# ProPrj_elrsTransmitter_2026-04-23.net
KiCad netlist of a schematic drawn in EasyEDA Pro
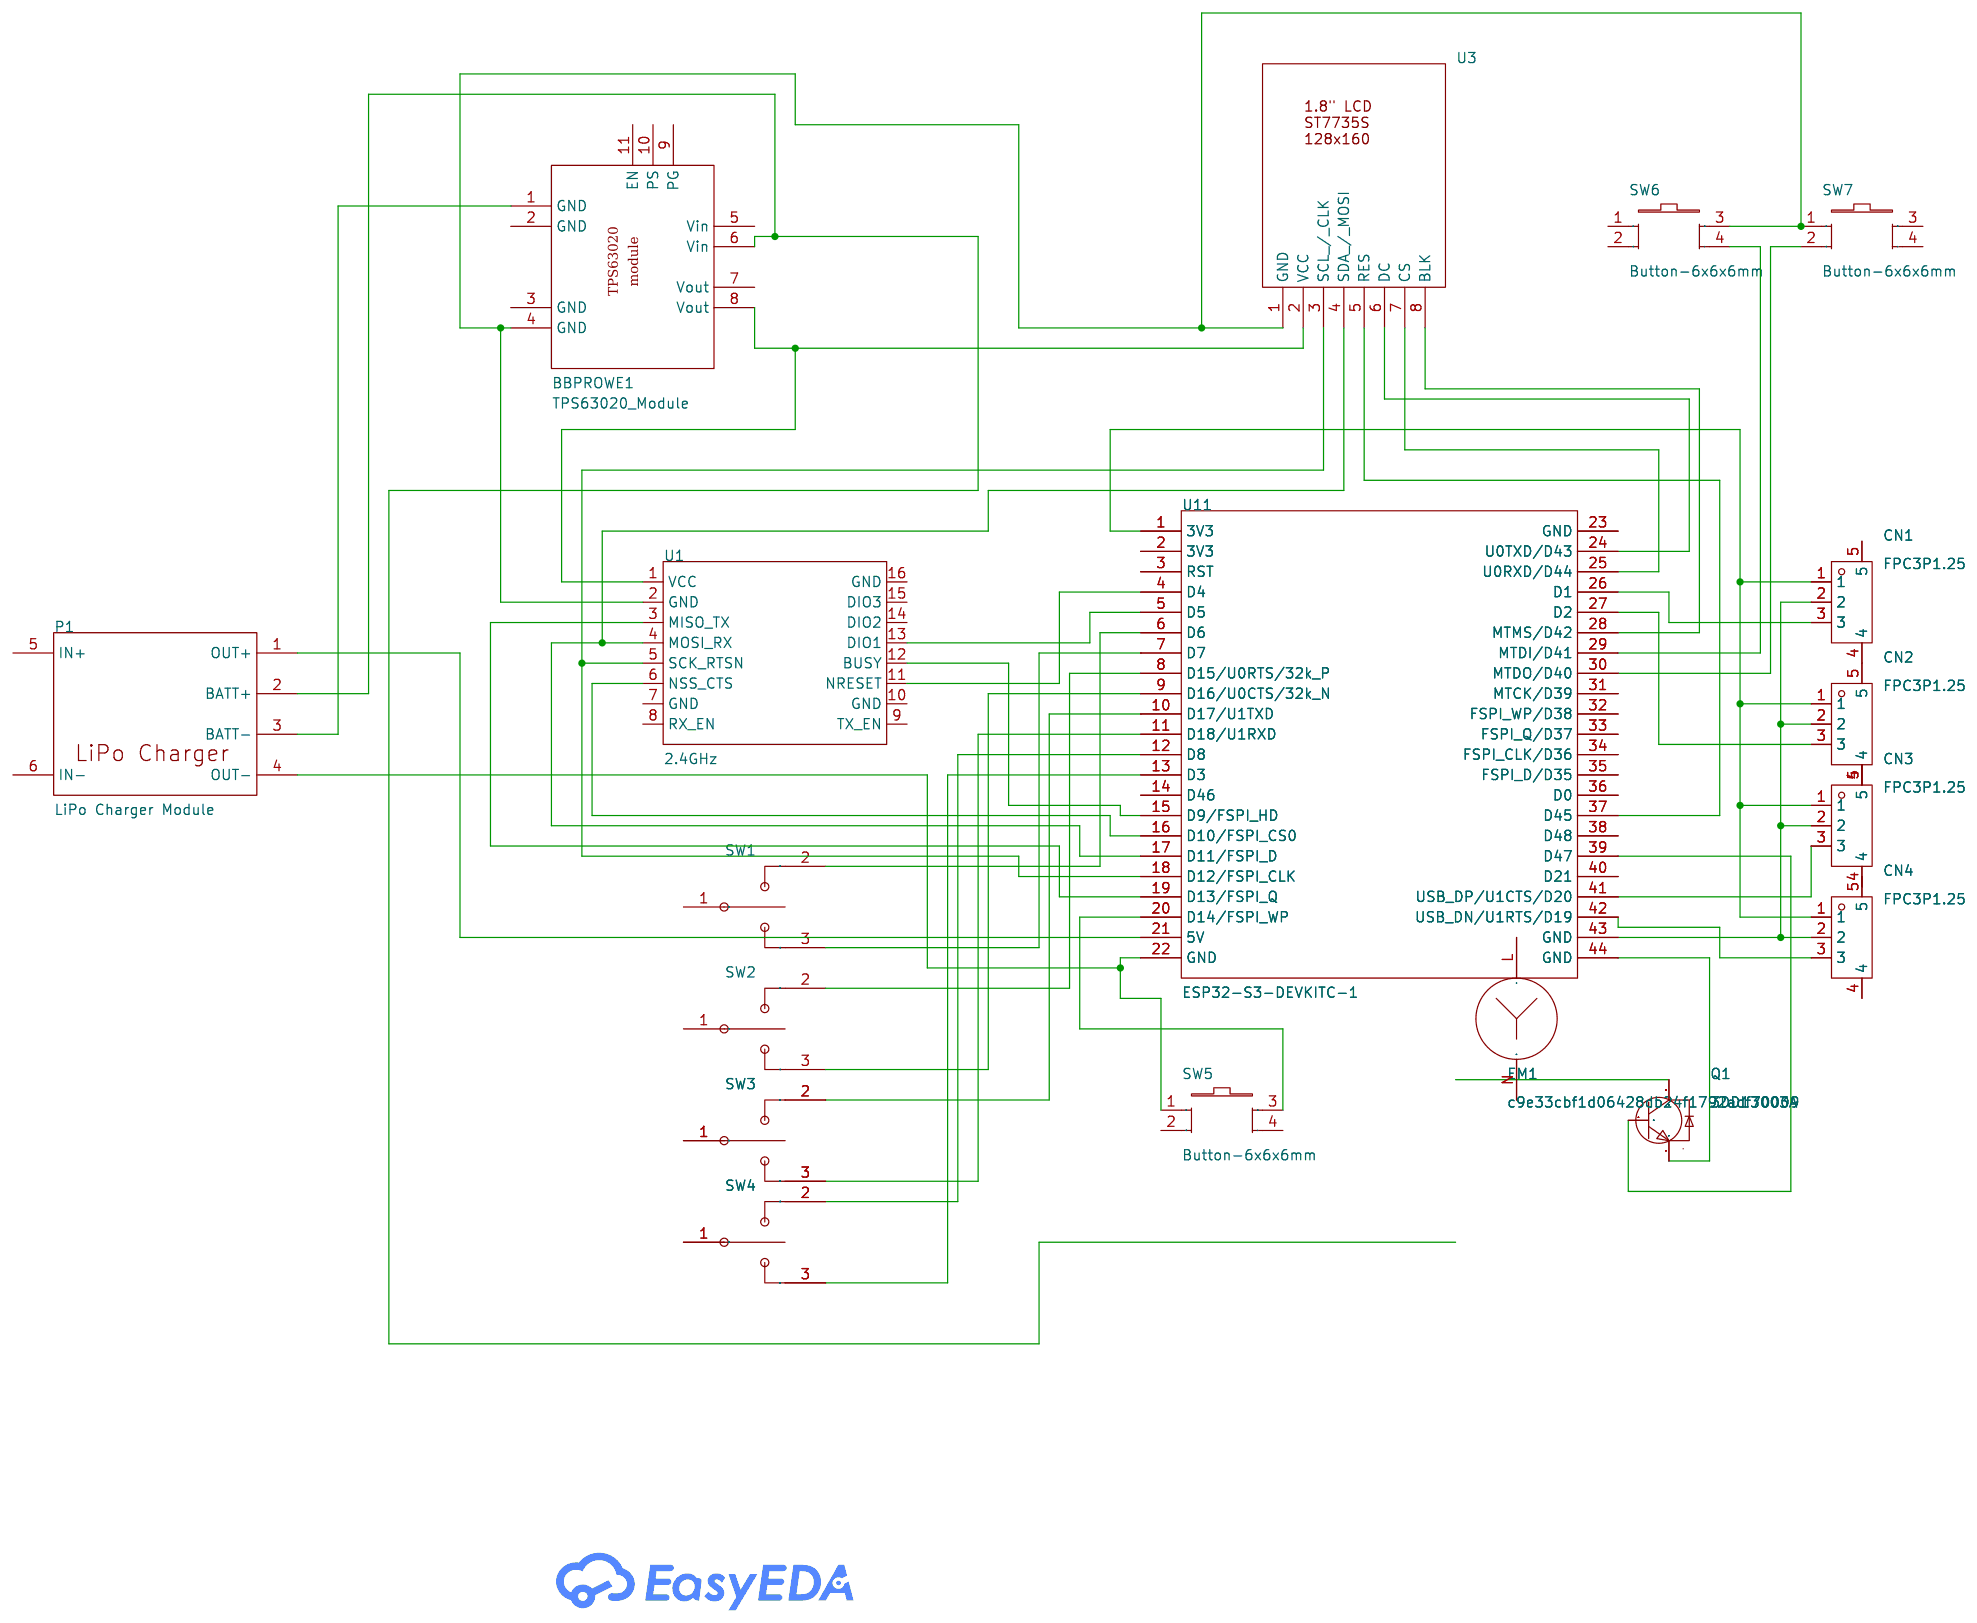
[diagram p0: schematic sheet]

(export (version "E")
  (design (tool "Eeschema 10.0.6"))
  (components
    (comp (ref "BBPROWE1")
      (value "TPS63020_Module")
      (footprint "easyedapro:TPS63020_MODULE_PCB")
      (libsource (lib "easyedapro") (part "TPS63020_Module"))
    )
    (comp (ref "CN1")
      (value "FPC3P1.25")
      (footprint "easyedapro:CONN-SMD_3P-P1.25_1.25T-3PWT")
      (libsource (lib "easyedapro") (part "FPC3P1.25"))
    )
    (comp (ref "CN2")
      (value "FPC3P1.25")
      (footprint "easyedapro:CONN-SMD_3P-P1.25_1.25T-3PWT")
      (libsource (lib "easyedapro") (part "FPC3P1.25"))
    )
    (comp (ref "CN3")
      (value "FPC3P1.25")
      (footprint "easyedapro:CONN-SMD_3P-P1.25_1.25T-3PWT")
      (libsource (lib "easyedapro") (part "FPC3P1.25"))
    )
    (comp (ref "CN4")
      (value "FPC3P1.25")
      (footprint "easyedapro:CONN-SMD_3P-P1.25_1.25T-3PWT")
      (libsource (lib "easyedapro") (part "FPC3P1.25"))
    )
    (comp (ref "EM1")
      (value "c9e33cbf1d06428db24f1792adf70009")
      (description "GVI AC Fan for half size server rack")
      (fields (field (name "Manufacturer") "GVI"))
      (libsource (lib "easyedapro") (part "GVI AC Fan"))
    )
    (comp (ref "P1")
      (value "LiPo Charger Module")
      (footprint "easyedapro:LIPO CHARGER FOOTPRINT")
      (libsource (lib "easyedapro") (part "Charger Lipo"))
    )
    (comp (ref "Q1")
      (value "3DD13003A")
      (footprint "easyedapro:TO-92-3_L4.8-W3.7-P1.27-L")
      (fields (field (name "Manufacturer") "吉林华微"))
      (libsource (lib "easyedapro") (part "3DD13003A"))
    )
    (comp (ref "SW1")
      (value "~")
      (footprint "easyedapro:3_Pin_Toggle_Switch_Footprint")
      (libsource (lib "easyedapro") (part "3_Position_Toggle_Switch"))
    )
    (comp (ref "SW2")
      (value "~")
      (footprint "easyedapro:3_Pin_Toggle_Switch_Footprint")
      (libsource (lib "easyedapro") (part "3_Position_Toggle_Switch"))
    )
    (comp (ref "SW3")
      (value "~")
      (footprint "easyedapro:3_Pin_Toggle_Switch_Footprint")
      (libsource (lib "easyedapro") (part "3_Position_Toggle_Switch"))
    )
    (comp (ref "SW4")
      (value "~")
      (footprint "easyedapro:3_Pin_Toggle_Switch_Footprint")
      (libsource (lib "easyedapro") (part "3_Position_Toggle_Switch"))
    )
    (comp (ref "SW5")
      (value "Button-6x6x6mm")
      (footprint "easyedapro:SW-TH_4PIN-L6.00-W6.00")
      (fields
        (field (name "Manufacturer Part") "Switch,6*6*6Plastic head,260G, 0.25mm,Straight line")
        (field (name "Manufacturer") "BBJ")
      )
      (libsource (lib "easyedapro") (part "Button-6x6x6mm"))
    )
    (comp (ref "SW6")
      (value "Button-6x6x6mm")
      (footprint "easyedapro:SW-TH_4PIN-L6.00-W6.00")
      (fields
        (field (name "Manufacturer Part") "Switch,6*6*6Plastic head,260G, 0.25mm,Straight line")
        (field (name "Manufacturer") "BBJ")
      )
      (libsource (lib "easyedapro") (part "Button-6x6x6mm"))
    )
    (comp (ref "SW7")
      (value "Button-6x6x6mm")
      (footprint "easyedapro:SW-TH_4PIN-L6.00-W6.00")
      (fields
        (field (name "Manufacturer Part") "Switch,6*6*6Plastic head,260G, 0.25mm,Straight line")
        (field (name "Manufacturer") "BBJ")
      )
      (libsource (lib "easyedapro") (part "Button-6x6x6mm"))
    )
    (comp (ref "U1")
      (value "2.4GHz")
      (footprint "easyedapro:WIRELM-SMD_E28-2G4M27SX")
      (description "Frequency:2.4GHz")
      (fields (field (name "Manufacturer Part") "E28-2G4M27SX") (field (name "Manufacturer") "EBYTE(亿佰特)"))
      (libsource (lib "easyedapro") (part "E28-2G4M27SX"))
    )
    (comp (ref "U3")
      (value "~")
      (footprint "easyedapro:WeAct 1.8 inch TFT ST7735S")
      (libsource (lib "easyedapro") (part "IPS_LCD_1.8_ST7735S_128x160"))
    )
    (comp (ref "U11")
      (value "ESP32-S3-DEVKITC-1")
      (footprint "easyedapro:ESP32-S3-DEVKITC-1")
      (fields
        (field (name "Manufacturer Part") "ESP32-S3-DEVKITC-1U-N8R8")
        (field (name "Manufacturer") "Espressif")
      )
      (libsource (lib "easyedapro") (part "ESP32-S3-DEVKITC-1"))
    )
  )
  (nets
    (net (code "1") (name "Net-(CN1-Pad1)") (class "Default")
      (node (ref "CN1") (pin "1") (pinfunction "1_1") (pintype "unspecified"))
      (node (ref "CN2") (pin "1") (pinfunction "1_1") (pintype "unspecified"))
      (node (ref "CN3") (pin "1") (pinfunction "1_1") (pintype "unspecified"))
      (node (ref "CN4") (pin "1") (pinfunction "1_1") (pintype "unspecified"))
      (node (ref "U11") (pin "1") (pinfunction "3V3_1") (pintype "input"))
    )
    (net (code "2") (name "Net-(CN1-Pad2)") (class "Default")
      (node (ref "CN1") (pin "2") (pinfunction "2_2") (pintype "unspecified"))
      (node (ref "CN2") (pin "2") (pinfunction "2_2") (pintype "unspecified"))
      (node (ref "CN3") (pin "2") (pinfunction "2_2") (pintype "unspecified"))
      (node (ref "CN4") (pin "2") (pinfunction "2_2") (pintype "unspecified"))
      (node (ref "U11") (pin "43") (pinfunction "GND_43") (pintype "input"))
    )
    (net (code "3") (name "Net-(CN1-Pad4)") (class "Default")
      (node (ref "CN1") (pin "4") (pinfunction "4_4") (pintype "unspecified"))
      (node (ref "CN2") (pin "5") (pinfunction "5_5") (pintype "unspecified"))
    )
    (net (code "4") (name "Net-(P1-BATT+)") (class "Default")
      (node (ref "BBPROWE1") (pin "6") (pinfunction "Vin_6") (pintype "input"))
      (node (ref "P1") (pin "2") (pinfunction "BATT+_2") (pintype "unspecified"))
    )
    (net (code "5") (name "Net-(P1-BATT-)") (class "Default")
      (node (ref "BBPROWE1") (pin "1") (pinfunction "GND_1") (pintype "input"))
      (node (ref "P1") (pin "3") (pinfunction "BATT-_3") (pintype "unspecified"))
    )
    (net (code "6") (name "Net-(P1-OUT+)") (class "Default")
      (node (ref "P1") (pin "1") (pinfunction "OUT+_1") (pintype "unspecified"))
      (node (ref "U11") (pin "21") (pinfunction "5V_21") (pintype "bidirectional"))
    )
    (net (code "7") (name "Net-(P1-OUT-)") (class "Default")
      (node (ref "P1") (pin "4") (pinfunction "OUT-_4") (pintype "unspecified"))
      (node (ref "SW5") (pin "1") (pinfunction "1_1") (pintype "input"))
      (node (ref "U11") (pin "22") (pinfunction "GND_22") (pintype "bidirectional"))
    )
    (net (code "8") (name "Net-(Q1-B)") (class "Default")
      (node (ref "Q1") (pin "3") (pinfunction "B_3") (pintype "unspecified"))
      (node (ref "U11") (pin "39") (pinfunction "D47_39") (pintype "input"))
    )
    (net (code "9") (name "Net-(Q1-E)") (class "Default")
      (node (ref "Q1") (pin "1") (pinfunction "E_1") (pintype "unspecified"))
      (node (ref "U11") (pin "44") (pinfunction "GND_44") (pintype "input"))
    )
    (net (code "10") (name "Net-(U1-BUSY)") (class "Default")
      (node (ref "U1") (pin "12") (pinfunction "BUSY_12") (pintype "unspecified"))
      (node (ref "U11") (pin "15") (pinfunction "D9/FSPI_HD_15") (pintype "bidirectional"))
    )
    (net (code "11") (name "Net-(U1-DIO1)") (class "Default")
      (node (ref "U1") (pin "13") (pinfunction "DIO1_13") (pintype "unspecified"))
      (node (ref "U11") (pin "5") (pinfunction "D5_5") (pintype "bidirectional"))
    )
    (net (code "12") (name "Net-(U1-MISO_TX)") (class "Default")
      (node (ref "U1") (pin "3") (pinfunction "MISO_TX_3") (pintype "unspecified"))
      (node (ref "U11") (pin "19") (pinfunction "D13/FSPI_Q_19") (pintype "input"))
    )
    (net (code "13") (name "Net-(U1-MOSI_RX)") (class "Default")
      (node (ref "U1") (pin "4") (pinfunction "MOSI_RX_4") (pintype "unspecified"))
      (node (ref "U11") (pin "17") (pinfunction "D11/FSPI_D_17") (pintype "bidirectional"))
      (node (ref "U3") (pin "4") (pinfunction "SDA_/_MOSI_4") (pintype "input"))
    )
    (net (code "14") (name "Net-(U1-NRESET)") (class "Default")
      (node (ref "U1") (pin "11") (pinfunction "NRESET_11") (pintype "unspecified"))
      (node (ref "U11") (pin "4") (pinfunction "D4_4") (pintype "bidirectional"))
    )
    (net (code "15") (name "Net-(U1-NSS_CTS)") (class "Default")
      (node (ref "U1") (pin "6") (pinfunction "NSS_CTS_6") (pintype "unspecified"))
      (node (ref "U11") (pin "16") (pinfunction "D10/FSPI_CS0_16") (pintype "bidirectional"))
    )
    (net (code "16") (name "Net-(U1-SCK_RTSN)") (class "Default")
      (node (ref "U1") (pin "5") (pinfunction "SCK_RTSN_5") (pintype "unspecified"))
      (node (ref "U11") (pin "18") (pinfunction "D12/FSPI_CLK_18") (pintype "input"))
      (node (ref "U3") (pin "3") (pinfunction "SCL_/_CLK_3") (pintype "input"))
    )
    (net (code "17") (name "Net-(U1-VCC)") (class "Default")
      (node (ref "BBPROWE1") (pin "8") (pinfunction "Vout_8") (pintype "input"))
      (node (ref "U1") (pin "1") (pinfunction "VCC_1") (pintype "unspecified"))
      (node (ref "U3") (pin "2") (pinfunction "VCC_2") (pintype "input"))
    )
    (net (code "18") (name "Net-(U3-GND)") (class "Default")
      (node (ref "BBPROWE1") (pin "4") (pinfunction "GND_4") (pintype "input"))
      (node (ref "SW6") (pin "3") (pinfunction "3_3") (pintype "input"))
      (node (ref "SW7") (pin "1") (pinfunction "1_1") (pintype "input"))
      (node (ref "U1") (pin "2") (pinfunction "GND_2") (pintype "unspecified"))
      (node (ref "U3") (pin "1") (pinfunction "GND_1") (pintype "input"))
    )
    (net (code "19") (name "Net-(U11-D1)") (class "Default")
      (node (ref "CN1") (pin "3") (pinfunction "3_3") (pintype "unspecified"))
      (node (ref "U11") (pin "26") (pinfunction "D1_26") (pintype "input"))
    )
    (net (code "20") (name "Net-(U11-D2)") (class "Default")
      (node (ref "CN2") (pin "3") (pinfunction "3_3") (pintype "unspecified"))
      (node (ref "U11") (pin "27") (pinfunction "D2_27") (pintype "bidirectional"))
    )
    (net (code "21") (name "Net-(U11-D3)") (class "Default")
      (node (ref "SW4") (pin "3") (pinfunction "3_3") (pintype "unspecified"))
      (node (ref "U11") (pin "13") (pinfunction "D3_13") (pintype "bidirectional"))
    )
    (net (code "22") (name "Net-(U11-D6)") (class "Default")
      (node (ref "SW1") (pin "2") (pinfunction "2_2") (pintype "unspecified"))
      (node (ref "U11") (pin "6") (pinfunction "D6_6") (pintype "bidirectional"))
    )
    (net (code "23") (name "Net-(U11-D7)") (class "Default")
      (node (ref "SW1") (pin "3") (pinfunction "3_3") (pintype "unspecified"))
      (node (ref "U11") (pin "7") (pinfunction "D7_7") (pintype "bidirectional"))
    )
    (net (code "24") (name "Net-(U11-D8)") (class "Default")
      (node (ref "SW4") (pin "2") (pinfunction "2_2") (pintype "unspecified"))
      (node (ref "U11") (pin "12") (pinfunction "D8_12") (pintype "bidirectional"))
    )
    (net (code "25") (name "Net-(U11-D14{slash}FSPI_WP)") (class "Default")
      (node (ref "SW5") (pin "3") (pinfunction "3_3") (pintype "input"))
      (node (ref "U11") (pin "20") (pinfunction "D14/FSPI_WP_20") (pintype "input"))
    )
    (net (code "26") (name "Net-(U11-D15{slash}U0RTS{slash}32k_P)") (class "Default")
      (node (ref "SW2") (pin "2") (pinfunction "2_2") (pintype "unspecified"))
      (node (ref "U11") (pin "8") (pinfunction "D15/U0RTS/32k_P_8") (pintype "bidirectional"))
    )
    (net (code "27") (name "Net-(U11-D16{slash}U0CTS{slash}32k_N)") (class "Default")
      (node (ref "SW2") (pin "3") (pinfunction "3_3") (pintype "unspecified"))
      (node (ref "U11") (pin "9") (pinfunction "D16/U0CTS/32k_N_9") (pintype "bidirectional"))
    )
    (net (code "28") (name "Net-(U11-D17{slash}U1TXD)") (class "Default")
      (node (ref "SW3") (pin "2") (pinfunction "2_2") (pintype "unspecified"))
      (node (ref "U11") (pin "10") (pinfunction "D17/U1TXD_10") (pintype "bidirectional"))
    )
    (net (code "29") (name "Net-(U11-D18{slash}U1RXD)") (class "Default")
      (node (ref "SW3") (pin "3") (pinfunction "3_3") (pintype "unspecified"))
      (node (ref "U11") (pin "11") (pinfunction "D18/U1RXD_11") (pintype "bidirectional"))
    )
    (net (code "30") (name "Net-(U11-D45)") (class "Default")
      (node (ref "U11") (pin "37") (pinfunction "D45_37") (pintype "bidirectional"))
      (node (ref "U3") (pin "5") (pinfunction "RES_5") (pintype "input"))
    )
    (net (code "31") (name "Net-(U11-MTDI{slash}D41)") (class "Default")
      (node (ref "SW6") (pin "4") (pinfunction "4_4") (pintype "input"))
      (node (ref "U11") (pin "29") (pinfunction "MTDI/D41_29") (pintype "bidirectional"))
    )
    (net (code "32") (name "Net-(U11-MTDO{slash}D40)") (class "Default")
      (node (ref "SW7") (pin "2") (pinfunction "2_2") (pintype "input"))
      (node (ref "U11") (pin "30") (pinfunction "MTDO/D40_30") (pintype "bidirectional"))
    )
    (net (code "33") (name "Net-(U11-MTMS{slash}D42)") (class "Default")
      (node (ref "U11") (pin "28") (pinfunction "MTMS/D42_28") (pintype "bidirectional"))
      (node (ref "U3") (pin "8") (pinfunction "BLK_8") (pintype "input"))
    )
    (net (code "34") (name "Net-(U11-U0RXD{slash}D44)") (class "Default")
      (node (ref "U11") (pin "25") (pinfunction "U0RXD/D44_25") (pintype "bidirectional"))
      (node (ref "U3") (pin "7") (pinfunction "CS_7") (pintype "input"))
    )
    (net (code "35") (name "Net-(U11-U0TXD{slash}D43)") (class "Default")
      (node (ref "U11") (pin "24") (pinfunction "U0TXD/D43_24") (pintype "bidirectional"))
      (node (ref "U3") (pin "6") (pinfunction "DC_6") (pintype "input"))
    )
    (net (code "36") (name "Net-(U11-USB_DN{slash}U1RTS{slash}D19)") (class "Default")
      (node (ref "CN4") (pin "3") (pinfunction "3_3") (pintype "unspecified"))
      (node (ref "U11") (pin "42") (pinfunction "USB_DN/U1RTS/D19_42") (pintype "input"))
    )
    (net (code "37") (name "Net-(U11-USB_DP{slash}U1CTS{slash}D20)") (class "Default")
      (node (ref "CN3") (pin "3") (pinfunction "3_3") (pintype "unspecified"))
      (node (ref "U11") (pin "41") (pinfunction "USB_DP/U1CTS/D20_41") (pintype "input"))
    )
    (net (code "38") (name "unconnected-(BBPROWE1-EN-Pad11)") (class "Default")
      (node (ref "BBPROWE1") (pin "11") (pinfunction "EN_11") (pintype "input"))
    )
    (net (code "39") (name "unconnected-(BBPROWE1-GND-Pad2)") (class "Default")
      (node (ref "BBPROWE1") (pin "2") (pinfunction "GND_2") (pintype "input"))
    )
    (net (code "40") (name "unconnected-(BBPROWE1-GND-Pad3)") (class "Default")
      (node (ref "BBPROWE1") (pin "3") (pinfunction "GND_3") (pintype "input"))
    )
    (net (code "41") (name "unconnected-(BBPROWE1-PG-Pad9)") (class "Default")
      (node (ref "BBPROWE1") (pin "9") (pinfunction "PG_9") (pintype "input"))
    )
    (net (code "42") (name "unconnected-(BBPROWE1-PS-Pad10)") (class "Default")
      (node (ref "BBPROWE1") (pin "10") (pinfunction "PS_10") (pintype "input"))
    )
    (net (code "43") (name "unconnected-(BBPROWE1-Vin-Pad5)") (class "Default")
      (node (ref "BBPROWE1") (pin "5") (pinfunction "Vin_5") (pintype "input"))
    )
    (net (code "44") (name "unconnected-(BBPROWE1-Vout-Pad7)") (class "Default")
      (node (ref "BBPROWE1") (pin "7") (pinfunction "Vout_7") (pintype "input"))
    )
    (net (code "45") (name "unconnected-(CN1-Pad5)") (class "Default")
      (node (ref "CN1") (pin "5") (pinfunction "5_5") (pintype "unspecified"))
    )
    (net (code "46") (name "unconnected-(CN2-Pad4)") (class "Default")
      (node (ref "CN2") (pin "4") (pinfunction "4_4") (pintype "unspecified"))
    )
    (net (code "47") (name "unconnected-(CN3-Pad4)") (class "Default")
      (node (ref "CN3") (pin "4") (pinfunction "4_4") (pintype "unspecified"))
    )
    (net (code "48") (name "unconnected-(CN3-Pad5)") (class "Default")
      (node (ref "CN3") (pin "5") (pinfunction "5_5") (pintype "unspecified"))
    )
    (net (code "49") (name "unconnected-(CN4-Pad4)") (class "Default")
      (node (ref "CN4") (pin "4") (pinfunction "4_4") (pintype "unspecified"))
    )
    (net (code "50") (name "unconnected-(CN4-Pad5)") (class "Default")
      (node (ref "CN4") (pin "5") (pinfunction "5_5") (pintype "unspecified"))
    )
    (net (code "51") (name "unconnected-(EM1-PadL)") (class "Default")
      (node (ref "EM1") (pin "L") (pinfunction "L_L") (pintype "input"))
    )
    (net (code "52") (name "unconnected-(EM1-PadN)") (class "Default")
      (node (ref "EM1") (pin "N") (pinfunction "N_N") (pintype "input"))
    )
    (net (code "53") (name "unconnected-(P1-IN+-Pad5)") (class "Default")
      (node (ref "P1") (pin "5") (pinfunction "IN+_5") (pintype "unspecified"))
    )
    (net (code "54") (name "unconnected-(P1-IN--Pad6)") (class "Default")
      (node (ref "P1") (pin "6") (pinfunction "IN-_6") (pintype "unspecified"))
    )
    (net (code "55") (name "unconnected-(Q1-C-Pad2)") (class "Default")
      (node (ref "Q1") (pin "2") (pinfunction "C_2") (pintype "unspecified"))
    )
    (net (code "56") (name "unconnected-(SW1-Pad1)") (class "Default")
      (node (ref "SW1") (pin "1") (pinfunction "1_1") (pintype "unspecified"))
    )
    (net (code "57") (name "unconnected-(SW2-Pad1)") (class "Default")
      (node (ref "SW2") (pin "1") (pinfunction "1_1") (pintype "unspecified"))
    )
    (net (code "58") (name "unconnected-(SW3-Pad1)") (class "Default")
      (node (ref "SW3") (pin "1") (pinfunction "1_1") (pintype "unspecified"))
    )
    (net (code "59") (name "unconnected-(SW4-Pad1)") (class "Default")
      (node (ref "SW4") (pin "1") (pinfunction "1_1") (pintype "unspecified"))
    )
    (net (code "60") (name "unconnected-(SW5-Pad2)") (class "Default")
      (node (ref "SW5") (pin "2") (pinfunction "2_2") (pintype "input"))
    )
    (net (code "61") (name "unconnected-(SW5-Pad4)") (class "Default")
      (node (ref "SW5") (pin "4") (pinfunction "4_4") (pintype "input"))
    )
    (net (code "62") (name "unconnected-(SW6-Pad1)") (class "Default")
      (node (ref "SW6") (pin "1") (pinfunction "1_1") (pintype "input"))
    )
    (net (code "63") (name "unconnected-(SW6-Pad2)") (class "Default")
      (node (ref "SW6") (pin "2") (pinfunction "2_2") (pintype "input"))
    )
    (net (code "64") (name "unconnected-(SW7-Pad3)") (class "Default")
      (node (ref "SW7") (pin "3") (pinfunction "3_3") (pintype "input"))
    )
    (net (code "65") (name "unconnected-(SW7-Pad4)") (class "Default")
      (node (ref "SW7") (pin "4") (pinfunction "4_4") (pintype "input"))
    )
    (net (code "66") (name "unconnected-(U1-DIO2-Pad14)") (class "Default")
      (node (ref "U1") (pin "14") (pinfunction "DIO2_14") (pintype "unspecified"))
    )
    (net (code "67") (name "unconnected-(U1-DIO3-Pad15)") (class "Default")
      (node (ref "U1") (pin "15") (pinfunction "DIO3_15") (pintype "unspecified"))
    )
    (net (code "68") (name "unconnected-(U1-GND-Pad7)") (class "Default")
      (node (ref "U1") (pin "7") (pinfunction "GND_7") (pintype "unspecified"))
    )
    (net (code "69") (name "unconnected-(U1-GND-Pad10)") (class "Default")
      (node (ref "U1") (pin "10") (pinfunction "GND_10") (pintype "unspecified"))
    )
    (net (code "70") (name "unconnected-(U1-GND-Pad16)") (class "Default")
      (node (ref "U1") (pin "16") (pinfunction "GND_16") (pintype "unspecified"))
    )
    (net (code "71") (name "unconnected-(U1-RX_EN-Pad8)") (class "Default")
      (node (ref "U1") (pin "8") (pinfunction "RX_EN_8") (pintype "unspecified"))
    )
    (net (code "72") (name "unconnected-(U1-TX_EN-Pad9)") (class "Default")
      (node (ref "U1") (pin "9") (pinfunction "TX_EN_9") (pintype "unspecified"))
    )
    (net (code "73") (name "unconnected-(U11-3V3-Pad2)") (class "Default")
      (node (ref "U11") (pin "2") (pinfunction "3V3_2") (pintype "bidirectional"))
    )
    (net (code "74") (name "unconnected-(U11-D0-Pad36)") (class "Default")
      (node (ref "U11") (pin "36") (pinfunction "D0_36") (pintype "bidirectional"))
    )
    (net (code "75") (name "unconnected-(U11-D21-Pad40)") (class "Default")
      (node (ref "U11") (pin "40") (pinfunction "D21_40") (pintype "input"))
    )
    (net (code "76") (name "unconnected-(U11-D46-Pad14)") (class "Default")
      (node (ref "U11") (pin "14") (pinfunction "D46_14") (pintype "input"))
    )
    (net (code "77") (name "unconnected-(U11-D48-Pad38)") (class "Default")
      (node (ref "U11") (pin "38") (pinfunction "D48_38") (pintype "bidirectional"))
    )
    (net (code "78") (name "unconnected-(U11-FSPI_CLK{slash}D36-Pad34)") (class "Default")
      (node (ref "U11") (pin "34") (pinfunction "FSPI_CLK/D36_34") (pintype "bidirectional"))
    )
    (net (code "79") (name "unconnected-(U11-FSPI_D{slash}D35-Pad35)") (class "Default")
      (node (ref "U11") (pin "35") (pinfunction "FSPI_D/D35_35") (pintype "bidirectional"))
    )
    (net (code "80") (name "unconnected-(U11-FSPI_Q{slash}D37-Pad33)") (class "Default")
      (node (ref "U11") (pin "33") (pinfunction "FSPI_Q/D37_33") (pintype "bidirectional"))
    )
    (net (code "81") (name "unconnected-(U11-FSPI_WP{slash}D38-Pad32)") (class "Default")
      (node (ref "U11") (pin "32") (pinfunction "FSPI_WP/D38_32") (pintype "bidirectional"))
    )
    (net (code "82") (name "unconnected-(U11-GND-Pad23)") (class "Default")
      (node (ref "U11") (pin "23") (pinfunction "GND_23") (pintype "bidirectional"))
    )
    (net (code "83") (name "unconnected-(U11-MTCK{slash}D39-Pad31)") (class "Default")
      (node (ref "U11") (pin "31") (pinfunction "MTCK/D39_31") (pintype "bidirectional"))
    )
    (net (code "84") (name "unconnected-(U11-RST-Pad3)") (class "Default")
      (node (ref "U11") (pin "3") (pinfunction "RST_3") (pintype "bidirectional"))
    )
  )
)
